# love_o_meter.net
KiCad netlist of a schematic drawn in EAGLE
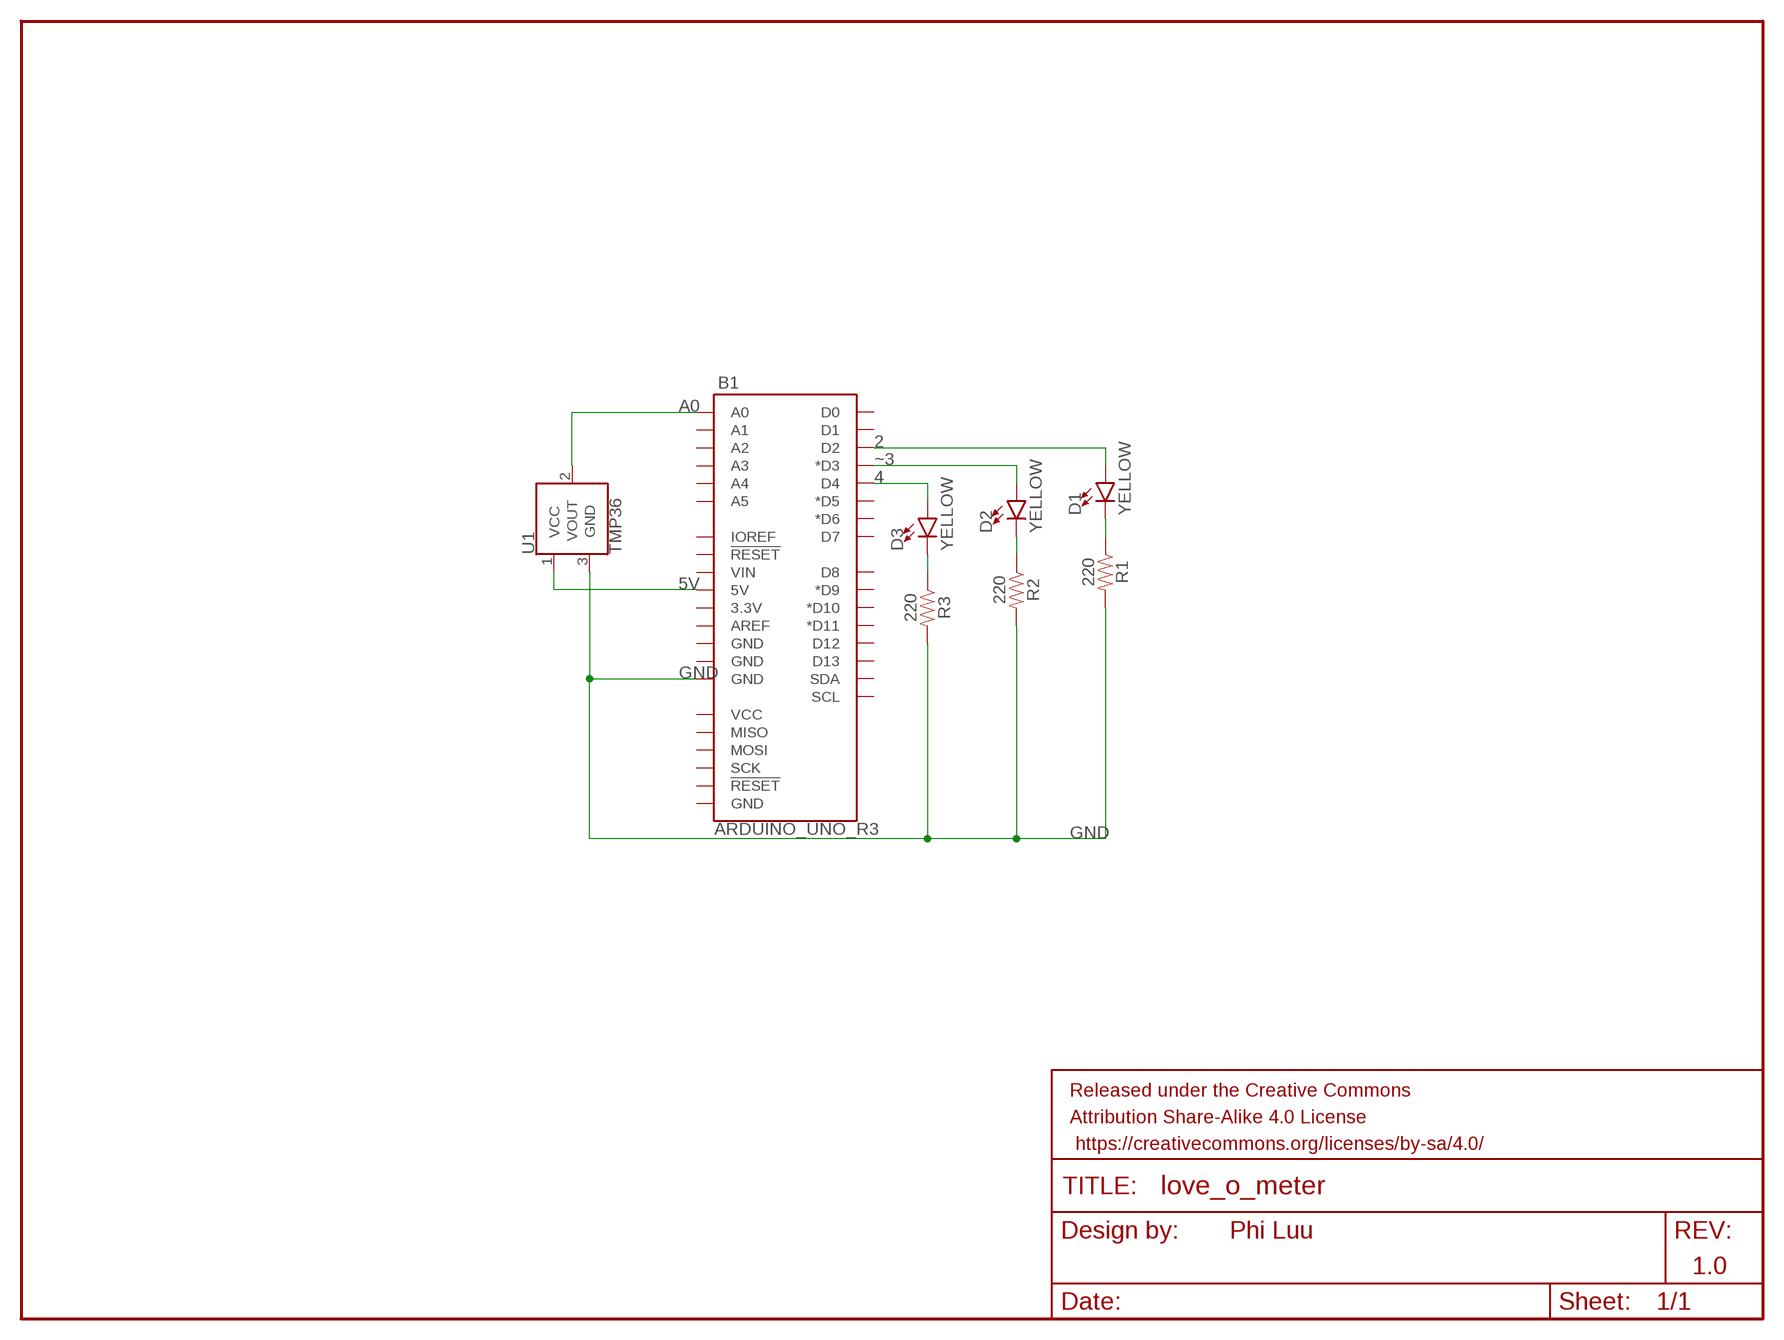
[diagram p0: schematic, sheet 1]

(export (version "E")
  (design (tool "Eeschema 10.0.6"))
  (components
    (comp (ref "B1")
      (value "ARDUINO_UNO_R3")
      (footprint "eagle-import:ARDUINO_R3")
      (libsource (lib "eagle-import") (part "ARDUINO_UNO_R3"))
    )
    (comp (ref "D1")
      (value "YELLOW")
      (footprint "eagle-import:LED_5MM")
      (libsource (lib "eagle-import") (part "LED5MM"))
    )
    (comp (ref "D2")
      (value "YELLOW")
      (footprint "eagle-import:LED_5MM")
      (libsource (lib "eagle-import") (part "LED5MM"))
    )
    (comp (ref "D3")
      (value "YELLOW")
      (footprint "eagle-import:LED_5MM")
      (libsource (lib "eagle-import") (part "LED5MM"))
    )
    (comp (ref "FRAME1")
      (value "FRAME-LETTER")
      (footprint "eagle-import:CREATIVE_COMMONS")
      (libsource (lib "eagle-import") (part "FRAME-LETTER"))
    )
    (comp (ref "R1")
      (value "220")
      (footprint "eagle-import:AXIAL-0.3")
      (libsource (lib "eagle-import") (part "1KOHM-HORIZ-1/4W-5%"))
    )
    (comp (ref "R2")
      (value "220")
      (footprint "eagle-import:AXIAL-0.3")
      (libsource (lib "eagle-import") (part "1KOHM-HORIZ-1/4W-5%"))
    )
    (comp (ref "R3")
      (value "220")
      (footprint "eagle-import:AXIAL-0.3")
      (libsource (lib "eagle-import") (part "1KOHM-HORIZ-1/4W-5%"))
    )
    (comp (ref "U1")
      (value "TMP36")
      (footprint "eagle-import:TO-92")
      (libsource (lib "eagle-import") (part "TMP36GT9"))
    )
  )
  (nets
    (net (code "1") (name "/2") (class "Default")
      (node (ref "B1") (pin "D2") (pinfunction "D2_D2") (pintype "bidirectional"))
      (node (ref "D1") (pin "A") (pinfunction "A_A") (pintype "passive"))
    )
    (net (code "2") (name "/4") (class "Default")
      (node (ref "B1") (pin "D4") (pinfunction "D4_D4") (pintype "bidirectional"))
      (node (ref "D3") (pin "A") (pinfunction "A_A") (pintype "passive"))
    )
    (net (code "3") (name "/5V") (class "Default")
      (node (ref "B1") (pin "5V") (pinfunction "5V_5V") (pintype "bidirectional"))
      (node (ref "U1") (pin "1") (pinfunction "VCC_1") (pintype "bidirectional"))
    )
    (net (code "4") (name "/A0") (class "Default")
      (node (ref "B1") (pin "A0") (pinfunction "A0_A0") (pintype "bidirectional"))
      (node (ref "U1") (pin "2") (pinfunction "VOUT_2") (pintype "bidirectional"))
    )
    (net (code "5") (name "/GND") (class "Default")
      (node (ref "B1") (pin "GND@2") (pinfunction "GND_GND@2") (pintype "bidirectional"))
      (node (ref "R1") (pin "P$2") (pinfunction "2_P$2") (pintype "passive"))
      (node (ref "R2") (pin "P$2") (pinfunction "2_P$2") (pintype "passive"))
      (node (ref "R3") (pin "P$2") (pinfunction "2_P$2") (pintype "passive"))
      (node (ref "U1") (pin "3") (pinfunction "GND_3") (pintype "bidirectional"))
    )
    (net (code "6") (name "/~{3}") (class "Default")
      (node (ref "B1") (pin "D3") (pinfunction "*D3_D3") (pintype "bidirectional"))
      (node (ref "D2") (pin "A") (pinfunction "A_A") (pintype "passive"))
    )
    (net (code "7") (name "Net-(D1-C)") (class "Default")
      (node (ref "D1") (pin "K") (pinfunction "C_K") (pintype "passive"))
      (node (ref "R1") (pin "P$1") (pinfunction "1_P$1") (pintype "passive"))
    )
    (net (code "8") (name "Net-(D2-C)") (class "Default")
      (node (ref "D2") (pin "K") (pinfunction "C_K") (pintype "passive"))
      (node (ref "R2") (pin "P$1") (pinfunction "1_P$1") (pintype "passive"))
    )
    (net (code "9") (name "Net-(D3-C)") (class "Default")
      (node (ref "D3") (pin "K") (pinfunction "C_K") (pintype "passive"))
      (node (ref "R3") (pin "P$1") (pinfunction "1_P$1") (pintype "passive"))
    )
    (net (code "10") (name "unconnected-(B1-*D5-PadD5)") (class "Default")
      (node (ref "B1") (pin "D5") (pinfunction "*D5_D5") (pintype "bidirectional"))
    )
    (net (code "11") (name "unconnected-(B1-*D6-PadD6)") (class "Default")
      (node (ref "B1") (pin "D6") (pinfunction "*D6_D6") (pintype "bidirectional"))
    )
    (net (code "12") (name "unconnected-(B1-*D9-PadD9)") (class "Default")
      (node (ref "B1") (pin "D9") (pinfunction "*D9_D9") (pintype "bidirectional"))
    )
    (net (code "13") (name "unconnected-(B1-*D10-PadD10)") (class "Default")
      (node (ref "B1") (pin "D10") (pinfunction "*D10_D10") (pintype "bidirectional"))
    )
    (net (code "14") (name "unconnected-(B1-*D11-PadD11)") (class "Default")
      (node (ref "B1") (pin "D11") (pinfunction "*D11_D11") (pintype "bidirectional"))
    )
    (net (code "15") (name "unconnected-(B1-GND-PadGND@1)") (class "Default")
      (node (ref "B1") (pin "GND@1") (pinfunction "GND_GND@1") (pintype "bidirectional"))
    )
    (net (code "16") (name "unconnected-(B1-GND-PadGND@3)") (class "Default")
      (node (ref "B1") (pin "GND@3") (pinfunction "GND_GND@3") (pintype "bidirectional"))
    )
    (net (code "17") (name "unconnected-(B1-GND-PadGND@4)") (class "Default")
      (node (ref "B1") (pin "GND@4") (pinfunction "GND_GND@4") (pintype "bidirectional"))
    )
    (net (code "18") (name "unconnected-(B1-Pad3.3V)") (class "Default")
      (node (ref "B1") (pin "3.3V") (pinfunction "3.3V_3.3V") (pintype "bidirectional"))
    )
    (net (code "19") (name "unconnected-(B1-PadA1)") (class "Default")
      (node (ref "B1") (pin "A1") (pinfunction "A1_A1") (pintype "bidirectional"))
    )
    (net (code "20") (name "unconnected-(B1-PadA2)") (class "Default")
      (node (ref "B1") (pin "A2") (pinfunction "A2_A2") (pintype "bidirectional"))
    )
    (net (code "21") (name "unconnected-(B1-PadA3)") (class "Default")
      (node (ref "B1") (pin "A3") (pinfunction "A3_A3") (pintype "bidirectional"))
    )
    (net (code "22") (name "unconnected-(B1-PadA4)") (class "Default")
      (node (ref "B1") (pin "A4") (pinfunction "A4_A4") (pintype "bidirectional"))
    )
    (net (code "23") (name "unconnected-(B1-PadA5)") (class "Default")
      (node (ref "B1") (pin "A5") (pinfunction "A5_A5") (pintype "bidirectional"))
    )
    (net (code "24") (name "unconnected-(B1-PadAREF)") (class "Default")
      (node (ref "B1") (pin "AREF") (pinfunction "AREF_AREF") (pintype "bidirectional"))
    )
    (net (code "25") (name "unconnected-(B1-PadD0)") (class "Default")
      (node (ref "B1") (pin "D0") (pinfunction "D0_D0") (pintype "bidirectional"))
    )
    (net (code "26") (name "unconnected-(B1-PadD1)") (class "Default")
      (node (ref "B1") (pin "D1") (pinfunction "D1_D1") (pintype "bidirectional"))
    )
    (net (code "27") (name "unconnected-(B1-PadD7)") (class "Default")
      (node (ref "B1") (pin "D7") (pinfunction "D7_D7") (pintype "bidirectional"))
    )
    (net (code "28") (name "unconnected-(B1-PadD8)") (class "Default")
      (node (ref "B1") (pin "D8") (pinfunction "D8_D8") (pintype "bidirectional"))
    )
    (net (code "29") (name "unconnected-(B1-PadD12)") (class "Default")
      (node (ref "B1") (pin "D12") (pinfunction "D12_D12") (pintype "bidirectional"))
    )
    (net (code "30") (name "unconnected-(B1-PadD13)") (class "Default")
      (node (ref "B1") (pin "D13") (pinfunction "D13_D13") (pintype "bidirectional"))
    )
    (net (code "31") (name "unconnected-(B1-PadIOREF)") (class "Default")
      (node (ref "B1") (pin "IOREF") (pinfunction "IOREF_IOREF") (pintype "bidirectional"))
    )
    (net (code "32") (name "unconnected-(B1-PadMISO)") (class "Default")
      (node (ref "B1") (pin "MISO") (pinfunction "MISO_MISO") (pintype "bidirectional"))
    )
    (net (code "33") (name "unconnected-(B1-PadMOSI)") (class "Default")
      (node (ref "B1") (pin "MOSI") (pinfunction "MOSI_MOSI") (pintype "bidirectional"))
    )
    (net (code "34") (name "unconnected-(B1-PadSCK)") (class "Default")
      (node (ref "B1") (pin "SCK") (pinfunction "SCK_SCK") (pintype "bidirectional"))
    )
    (net (code "35") (name "unconnected-(B1-PadSCL)") (class "Default")
      (node (ref "B1") (pin "SCL") (pinfunction "SCL_SCL") (pintype "bidirectional"))
    )
    (net (code "36") (name "unconnected-(B1-PadSDA)") (class "Default")
      (node (ref "B1") (pin "SDA") (pinfunction "SDA_SDA") (pintype "bidirectional"))
    )
    (net (code "37") (name "unconnected-(B1-PadVCC)") (class "Default")
      (node (ref "B1") (pin "VCC") (pinfunction "VCC_VCC") (pintype "bidirectional"))
    )
    (net (code "38") (name "unconnected-(B1-PadVIN)") (class "Default")
      (node (ref "B1") (pin "VIN") (pinfunction "VIN_VIN") (pintype "bidirectional"))
    )
    (net (code "39") (name "unconnected-(B1-~{RESET}-PadRESET@1)") (class "Default")
      (node (ref "B1") (pin "RESET@1") (pinfunction "~{RESET}_RESET@1") (pintype "bidirectional"))
    )
    (net (code "40") (name "unconnected-(B1-~{RESET}-PadRESET@2)") (class "Default")
      (node (ref "B1") (pin "RESET@2") (pinfunction "~{RESET}_RESET@2") (pintype "bidirectional"))
    )
  )
)
